# stm32f0-qfp32-devboard.net
KiCad netlist of a schematic drawn in EAGLE
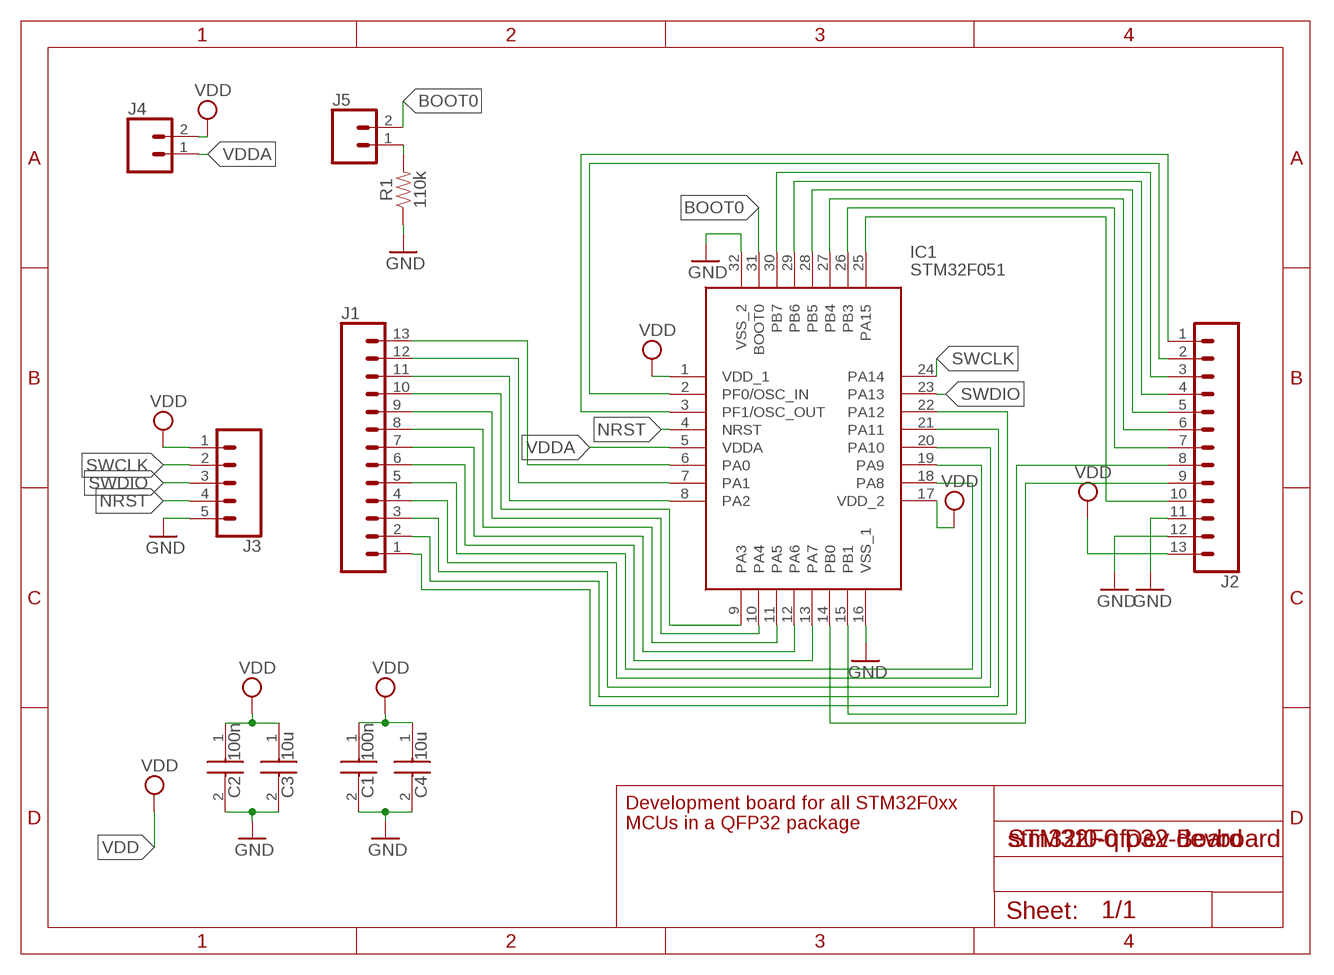
[diagram p0: schematic, sheet 1]

(export (version "E")
  (design (tool "Eeschema 10.0.6"))
  (components
    (comp (ref "C1")
      (value "100n")
      (footprint "eagle-import:CAPC2012X100N")
      (fields
        (field (name "MANUFACTURER_PART_NUMBER") "C2012X7R1H104K085AA")
        (field (name "MOUSER_PART_NUMBER") "810-C2012X7R1H104K-2")
      )
      (libsource (lib "eagle-import") (part "C2012X7R1H104K085AA"))
    )
    (comp (ref "C2")
      (value "100n")
      (footprint "eagle-import:CAPC2012X100N")
      (fields
        (field (name "MANUFACTURER_PART_NUMBER") "C2012X7R1H104K085AA")
        (field (name "MOUSER_PART_NUMBER") "810-C2012X7R1H104K-2")
      )
      (libsource (lib "eagle-import") (part "C2012X7R1H104K085AA"))
    )
    (comp (ref "C3")
      (value "10u")
      (footprint "eagle-import:CAPC3216X180N")
      (fields
        (field (name "MANUFACTURER_PART_NUMBER") "C3216X7R1C106K160AC")
        (field (name "MOUSER_PART_NUMBER") "810-C3216X7R1C106K")
      )
      (libsource (lib "eagle-import") (part "C3216X7R1C106K160AC"))
    )
    (comp (ref "C4")
      (value "10u")
      (footprint "eagle-import:CAPC3216X180N")
      (fields
        (field (name "MANUFACTURER_PART_NUMBER") "C3216X7R1C106K160AC")
        (field (name "MOUSER_PART_NUMBER") "810-C3216X7R1C106K")
      )
      (libsource (lib "eagle-import") (part "C3216X7R1C106K160AC"))
    )
    (comp (ref "IC1")
      (value "STM32F051")
      (footprint "eagle-import:QFP80P900X900X160-32N")
      (fields
        (field (name "MANUFACTURER_PART_NUMBER") "STM32F051K8T6")
        (field (name "MOUSER_PART_NUMBER") "511-STM32F051K8T6")
      )
      (libsource (lib "eagle-import") (part "STM32F051K8T6"))
    )
    (comp (ref "J1")
      (value "CONN_13")
      (footprint "eagle-import:1X13")
      (libsource (lib "eagle-import") (part "CONN_13"))
    )
    (comp (ref "J2")
      (value "CONN_13")
      (footprint "eagle-import:1X13")
      (libsource (lib "eagle-import") (part "CONN_13"))
    )
    (comp (ref "J3")
      (value "CONN_05")
      (footprint "eagle-import:1X05")
      (libsource (lib "eagle-import") (part "CONN_05"))
    )
    (comp (ref "J4")
      (value "CONN_02")
      (footprint "eagle-import:1X02")
      (libsource (lib "eagle-import") (part "CONN_02"))
    )
    (comp (ref "J5")
      (value "CONN_02")
      (footprint "eagle-import:1X02")
      (libsource (lib "eagle-import") (part "CONN_02"))
    )
    (comp (ref "R1")
      (value "110k")
      (footprint "eagle-import:0805")
      (libsource (lib "eagle-import") (part "0.22OHM-0805-1/4W-1%"))
    )
  )
  (nets
    (net (code "1") (name "BOOT0") (class "Default")
      (node (ref "IC1") (pin "31") (pinfunction "BOOT0_31") (pintype "bidirectional"))
      (node (ref "J5") (pin "2") (pinfunction "2_2") (pintype "passive"))
    )
    (net (code "2") (name "GND") (class "Default")
      (node (ref "C1") (pin "2") (pinfunction "2_2") (pintype "bidirectional"))
      (node (ref "C2") (pin "2") (pinfunction "2_2") (pintype "bidirectional"))
      (node (ref "C3") (pin "2") (pinfunction "2_2") (pintype "bidirectional"))
      (node (ref "C4") (pin "2") (pinfunction "2_2") (pintype "bidirectional"))
      (node (ref "IC1") (pin "16") (pinfunction "VSS_1_16") (pintype "power_in"))
      (node (ref "IC1") (pin "32") (pinfunction "VSS_2_32") (pintype "power_in"))
      (node (ref "J2") (pin "11") (pinfunction "11_11") (pintype "passive"))
      (node (ref "J2") (pin "12") (pinfunction "12_12") (pintype "passive"))
      (node (ref "J3") (pin "5") (pinfunction "5_5") (pintype "passive"))
      (node (ref "R1") (pin "1") (pinfunction "1_1") (pintype "passive"))
    )
    (net (code "3") (name "NRST") (class "Default")
      (node (ref "IC1") (pin "4") (pinfunction "NRST_4") (pintype "input"))
      (node (ref "J3") (pin "4") (pinfunction "4_4") (pintype "passive"))
    )
    (net (code "4") (name "Net-(IC1-PA0)") (class "Default")
      (node (ref "IC1") (pin "6") (pinfunction "PA0_6") (pintype "bidirectional"))
      (node (ref "J1") (pin "13") (pinfunction "13_13") (pintype "passive"))
    )
    (net (code "5") (name "Net-(IC1-PA1)") (class "Default")
      (node (ref "IC1") (pin "7") (pinfunction "PA1_7") (pintype "bidirectional"))
      (node (ref "J1") (pin "12") (pinfunction "12_12") (pintype "passive"))
    )
    (net (code "6") (name "Net-(IC1-PA2)") (class "Default")
      (node (ref "IC1") (pin "8") (pinfunction "PA2_8") (pintype "bidirectional"))
      (node (ref "J1") (pin "11") (pinfunction "11_11") (pintype "passive"))
    )
    (net (code "7") (name "Net-(IC1-PA3)") (class "Default")
      (node (ref "IC1") (pin "9") (pinfunction "PA3_9") (pintype "bidirectional"))
      (node (ref "J1") (pin "10") (pinfunction "10_10") (pintype "passive"))
    )
    (net (code "8") (name "Net-(IC1-PA4)") (class "Default")
      (node (ref "IC1") (pin "10") (pinfunction "PA4_10") (pintype "bidirectional"))
      (node (ref "J1") (pin "9") (pinfunction "9_9") (pintype "passive"))
    )
    (net (code "9") (name "Net-(IC1-PA5)") (class "Default")
      (node (ref "IC1") (pin "11") (pinfunction "PA5_11") (pintype "bidirectional"))
      (node (ref "J1") (pin "8") (pinfunction "8_8") (pintype "passive"))
    )
    (net (code "10") (name "Net-(IC1-PA6)") (class "Default")
      (node (ref "IC1") (pin "12") (pinfunction "PA6_12") (pintype "bidirectional"))
      (node (ref "J1") (pin "7") (pinfunction "7_7") (pintype "passive"))
    )
    (net (code "11") (name "Net-(IC1-PA7)") (class "Default")
      (node (ref "IC1") (pin "13") (pinfunction "PA7_13") (pintype "bidirectional"))
      (node (ref "J1") (pin "6") (pinfunction "6_6") (pintype "passive"))
    )
    (net (code "12") (name "Net-(IC1-PA8)") (class "Default")
      (node (ref "IC1") (pin "18") (pinfunction "PA8_18") (pintype "bidirectional"))
      (node (ref "J1") (pin "5") (pinfunction "5_5") (pintype "passive"))
    )
    (net (code "13") (name "Net-(IC1-PA9)") (class "Default")
      (node (ref "IC1") (pin "19") (pinfunction "PA9_19") (pintype "bidirectional"))
      (node (ref "J1") (pin "4") (pinfunction "4_4") (pintype "passive"))
    )
    (net (code "14") (name "Net-(IC1-PA10)") (class "Default")
      (node (ref "IC1") (pin "20") (pinfunction "PA10_20") (pintype "bidirectional"))
      (node (ref "J1") (pin "3") (pinfunction "3_3") (pintype "passive"))
    )
    (net (code "15") (name "Net-(IC1-PA11)") (class "Default")
      (node (ref "IC1") (pin "21") (pinfunction "PA11_21") (pintype "bidirectional"))
      (node (ref "J1") (pin "2") (pinfunction "2_2") (pintype "passive"))
    )
    (net (code "16") (name "Net-(IC1-PA12)") (class "Default")
      (node (ref "IC1") (pin "22") (pinfunction "PA12_22") (pintype "bidirectional"))
      (node (ref "J1") (pin "1") (pinfunction "1_1") (pintype "passive"))
    )
    (net (code "17") (name "Net-(IC1-PA15)") (class "Default")
      (node (ref "IC1") (pin "25") (pinfunction "PA15_25") (pintype "bidirectional"))
      (node (ref "J2") (pin "10") (pinfunction "10_10") (pintype "passive"))
    )
    (net (code "18") (name "Net-(IC1-PB0)") (class "Default")
      (node (ref "IC1") (pin "14") (pinfunction "PB0_14") (pintype "bidirectional"))
      (node (ref "J2") (pin "9") (pinfunction "9_9") (pintype "passive"))
    )
    (net (code "19") (name "Net-(IC1-PB1)") (class "Default")
      (node (ref "IC1") (pin "15") (pinfunction "PB1_15") (pintype "bidirectional"))
      (node (ref "J2") (pin "8") (pinfunction "8_8") (pintype "passive"))
    )
    (net (code "20") (name "Net-(IC1-PB3)") (class "Default")
      (node (ref "IC1") (pin "26") (pinfunction "PB3_26") (pintype "bidirectional"))
      (node (ref "J2") (pin "7") (pinfunction "7_7") (pintype "passive"))
    )
    (net (code "21") (name "Net-(IC1-PB4)") (class "Default")
      (node (ref "IC1") (pin "27") (pinfunction "PB4_27") (pintype "bidirectional"))
      (node (ref "J2") (pin "6") (pinfunction "6_6") (pintype "passive"))
    )
    (net (code "22") (name "Net-(IC1-PB5)") (class "Default")
      (node (ref "IC1") (pin "28") (pinfunction "PB5_28") (pintype "bidirectional"))
      (node (ref "J2") (pin "5") (pinfunction "5_5") (pintype "passive"))
    )
    (net (code "23") (name "Net-(IC1-PB6)") (class "Default")
      (node (ref "IC1") (pin "29") (pinfunction "PB6_29") (pintype "bidirectional"))
      (node (ref "J2") (pin "4") (pinfunction "4_4") (pintype "passive"))
    )
    (net (code "24") (name "Net-(IC1-PB7)") (class "Default")
      (node (ref "IC1") (pin "30") (pinfunction "PB7_30") (pintype "bidirectional"))
      (node (ref "J2") (pin "3") (pinfunction "3_3") (pintype "passive"))
    )
    (net (code "25") (name "Net-(IC1-PF0{slash}OSC_IN)") (class "Default")
      (node (ref "IC1") (pin "2") (pinfunction "PF0/OSC_IN_2") (pintype "input"))
      (node (ref "J2") (pin "2") (pinfunction "2_2") (pintype "passive"))
    )
    (net (code "26") (name "Net-(IC1-PF1{slash}OSC_OUT)") (class "Default")
      (node (ref "IC1") (pin "3") (pinfunction "PF1/OSC_OUT_3") (pintype "output"))
      (node (ref "J2") (pin "1") (pinfunction "1_1") (pintype "passive"))
    )
    (net (code "27") (name "Net-(J5-Pad1)") (class "Default")
      (node (ref "J5") (pin "1") (pinfunction "1_1") (pintype "passive"))
      (node (ref "R1") (pin "2") (pinfunction "2_2") (pintype "passive"))
    )
    (net (code "28") (name "SWCLK") (class "Default")
      (node (ref "IC1") (pin "24") (pinfunction "PA14_24") (pintype "bidirectional"))
      (node (ref "J3") (pin "2") (pinfunction "2_2") (pintype "passive"))
    )
    (net (code "29") (name "SWDIO") (class "Default")
      (node (ref "IC1") (pin "23") (pinfunction "PA13_23") (pintype "bidirectional"))
      (node (ref "J3") (pin "3") (pinfunction "3_3") (pintype "passive"))
    )
    (net (code "30") (name "VDD") (class "Default")
      (node (ref "C1") (pin "1") (pinfunction "1_1") (pintype "bidirectional"))
      (node (ref "C2") (pin "1") (pinfunction "1_1") (pintype "bidirectional"))
      (node (ref "C3") (pin "1") (pinfunction "1_1") (pintype "bidirectional"))
      (node (ref "C4") (pin "1") (pinfunction "1_1") (pintype "bidirectional"))
      (node (ref "IC1") (pin "1") (pinfunction "VDD_1_1") (pintype "power_in"))
      (node (ref "IC1") (pin "17") (pinfunction "VDD_2_17") (pintype "power_in"))
      (node (ref "J2") (pin "13") (pinfunction "13_13") (pintype "passive"))
      (node (ref "J3") (pin "1") (pinfunction "1_1") (pintype "passive"))
      (node (ref "J4") (pin "2") (pinfunction "2_2") (pintype "passive"))
    )
    (net (code "31") (name "VDDA") (class "Default")
      (node (ref "IC1") (pin "5") (pinfunction "VDDA_5") (pintype "power_in"))
      (node (ref "J4") (pin "1") (pinfunction "1_1") (pintype "passive"))
    )
  )
)
